# BLOCK5.net
KiCad netlist of a schematic drawn in Altium Designer
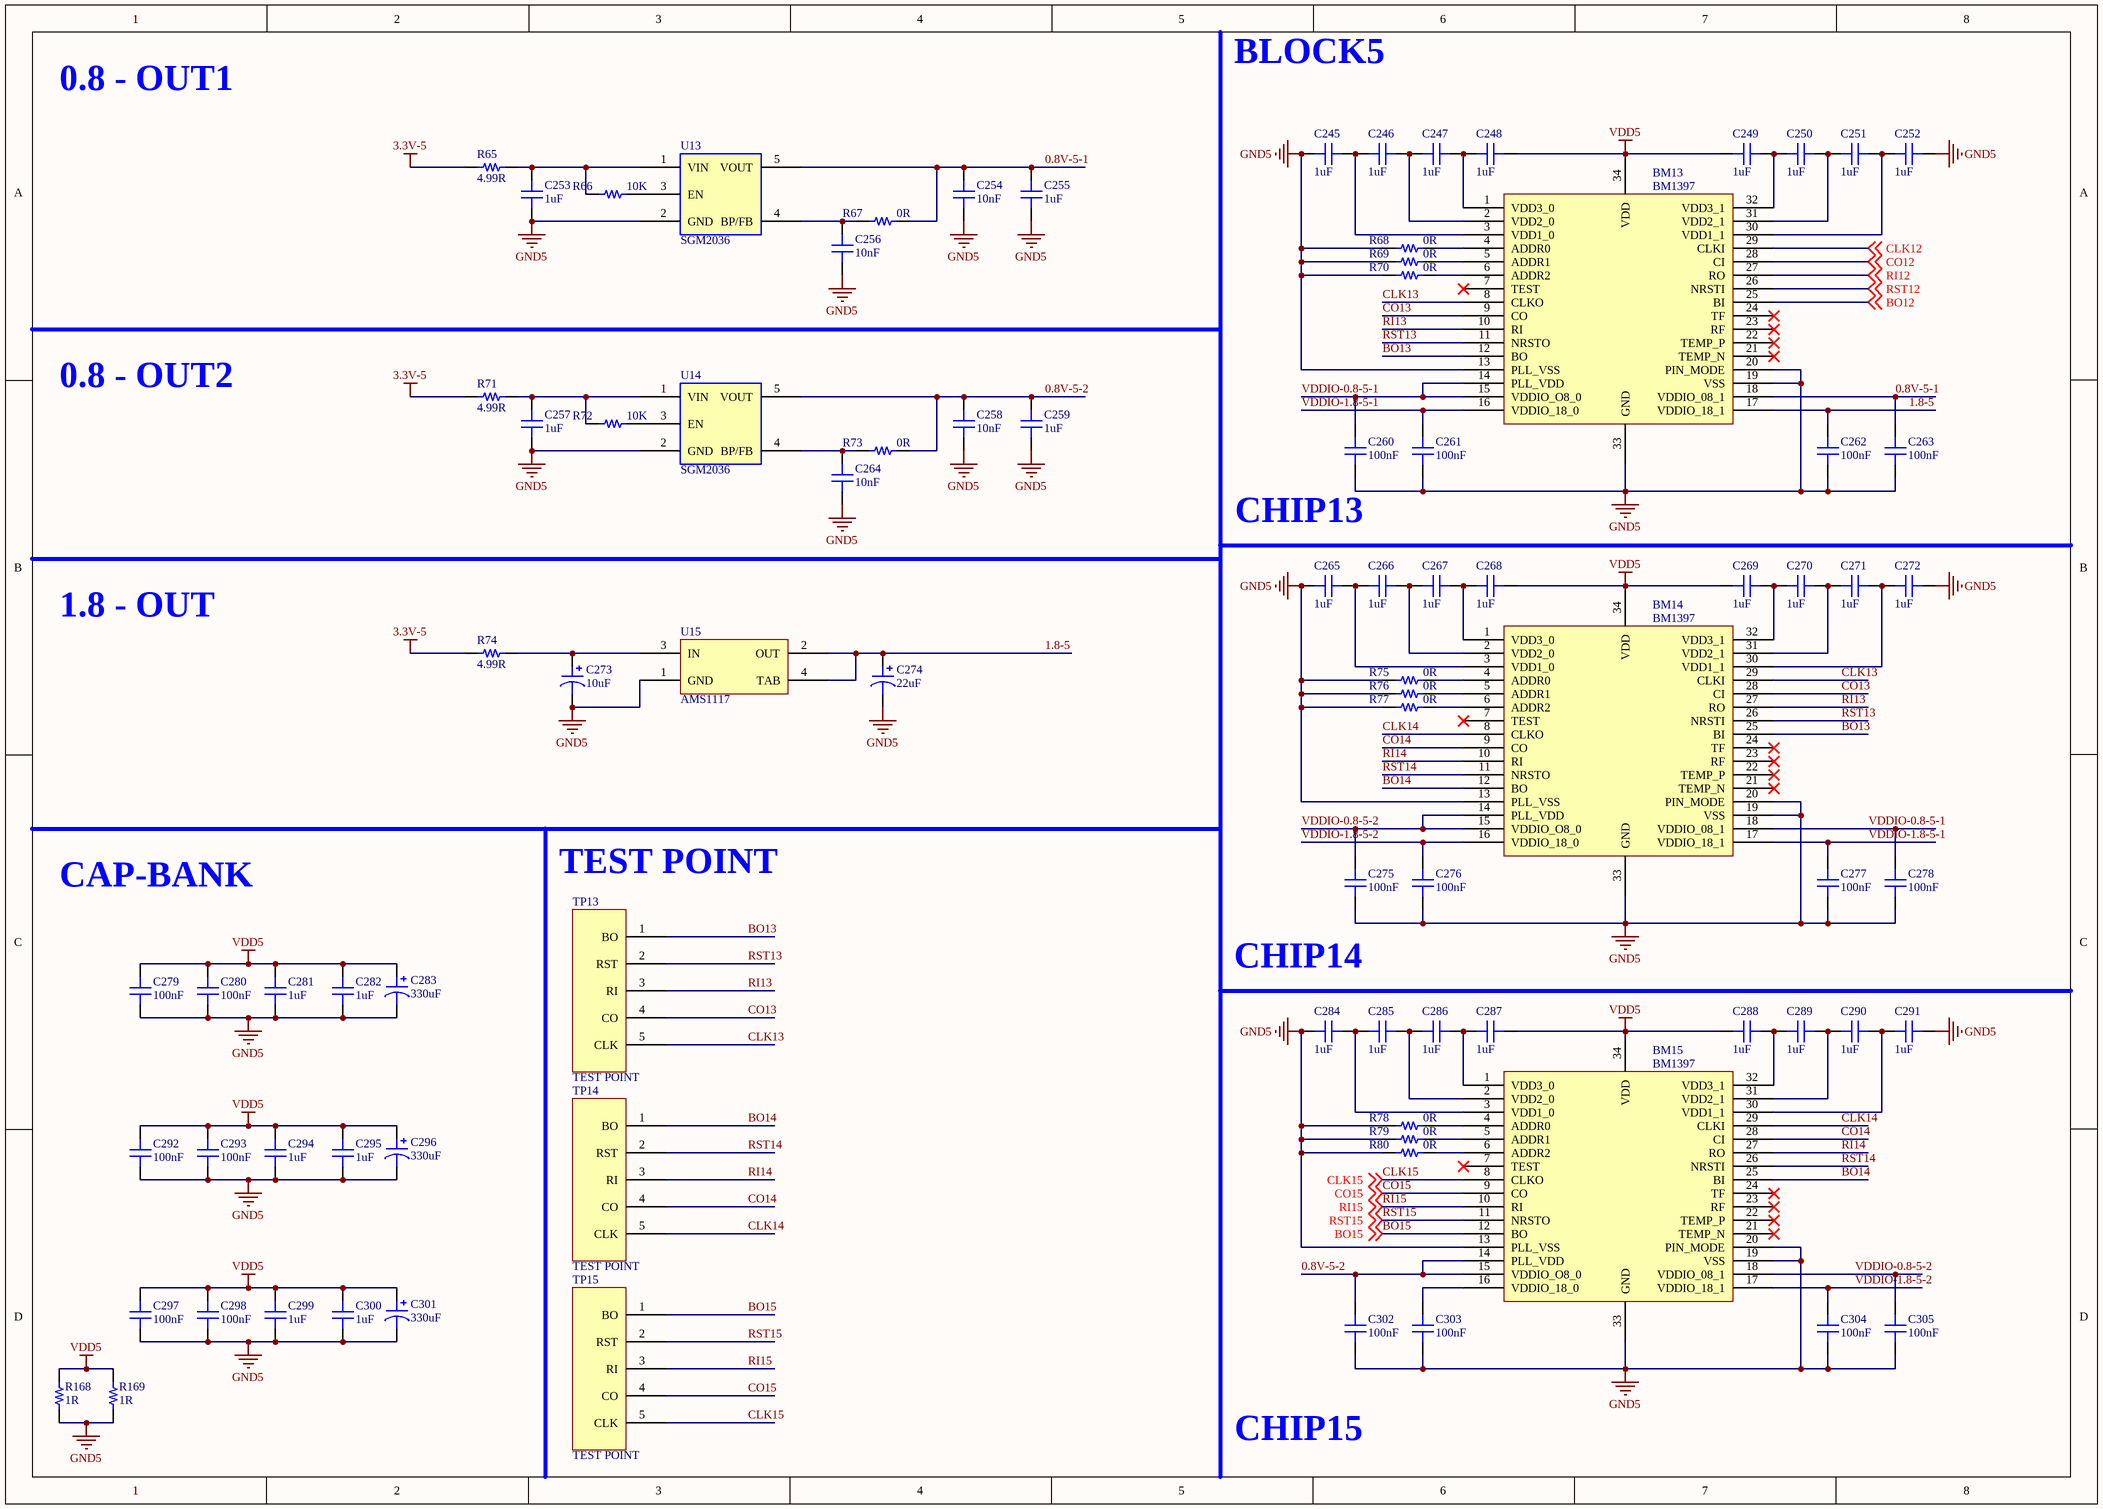
[diagram p0: BLOCK5.SchDoc]

(export (version "E")
  (design (tool "Eeschema 10.0.6"))
  (components
    (comp (ref "BM13") (value "BM1397") (footprint "BM1387") (libsource (lib "Miner_8TH") (part "BM1397_0")))
    (comp (ref "BM14") (value "BM1397") (footprint "BM1387") (libsource (lib "Miner_8TH") (part "BM1397_0")))
    (comp (ref "BM15") (value "BM1397") (footprint "BM1387") (libsource (lib "Miner_8TH") (part "BM1397_0")))
    (comp (ref "C245") (value "1uF") (footprint "CAP-SMD-0603") (libsource (lib "Miner_8TH") (part "CAP")))
    (comp (ref "C246") (value "1uF") (footprint "CAP-SMD-0603") (libsource (lib "Miner_8TH") (part "CAP")))
    (comp (ref "C247") (value "1uF") (footprint "CAP-SMD-0603") (libsource (lib "Miner_8TH") (part "CAP")))
    (comp (ref "C248") (value "1uF") (footprint "CAP-SMD-0603") (libsource (lib "Miner_8TH") (part "CAP")))
    (comp (ref "C249") (value "1uF") (footprint "CAP-SMD-0603") (libsource (lib "Miner_8TH") (part "CAP")))
    (comp (ref "C250") (value "1uF") (footprint "CAP-SMD-0603") (libsource (lib "Miner_8TH") (part "CAP")))
    (comp (ref "C251") (value "1uF") (footprint "CAP-SMD-0603") (libsource (lib "Miner_8TH") (part "CAP")))
    (comp (ref "C252") (value "1uF") (footprint "CAP-SMD-0603") (libsource (lib "Miner_8TH") (part "CAP")))
    (comp (ref "C253") (value "1uF") (footprint "CAP_SMD_0805") (libsource (lib "Miner_8TH") (part "CAP")))
    (comp (ref "C254") (value "10nF") (footprint "CAP_SMD_0805") (libsource (lib "Miner_8TH") (part "CAP")))
    (comp (ref "C255") (value "1uF") (footprint "CAP_SMD_0805") (libsource (lib "Miner_8TH") (part "CAP")))
    (comp (ref "C256") (value "10nF") (footprint "CAP_SMD_0805") (libsource (lib "Miner_8TH") (part "CAP")))
    (comp (ref "C257") (value "1uF") (footprint "CAP_SMD_0805") (libsource (lib "Miner_8TH") (part "CAP")))
    (comp (ref "C258") (value "10nF") (footprint "CAP_SMD_0805") (libsource (lib "Miner_8TH") (part "CAP")))
    (comp (ref "C259") (value "1uF") (footprint "CAP_SMD_0805") (libsource (lib "Miner_8TH") (part "CAP")))
    (comp (ref "C260") (value "100nF") (footprint "CAP_SMD_0805") (libsource (lib "Miner_8TH") (part "CAP")))
    (comp (ref "C261") (value "100nF") (footprint "CAP_SMD_0805") (libsource (lib "Miner_8TH") (part "CAP")))
    (comp (ref "C262") (value "100nF") (footprint "CAP_SMD_0805") (libsource (lib "Miner_8TH") (part "CAP")))
    (comp (ref "C263") (value "100nF") (footprint "CAP_SMD_0805") (libsource (lib "Miner_8TH") (part "CAP")))
    (comp (ref "C264") (value "10nF") (footprint "CAP_SMD_0805") (libsource (lib "Miner_8TH") (part "CAP")))
    (comp (ref "C265") (value "1uF") (footprint "CAP-SMD-0603") (libsource (lib "Miner_8TH") (part "CAP")))
    (comp (ref "C266") (value "1uF") (footprint "CAP-SMD-0603") (libsource (lib "Miner_8TH") (part "CAP")))
    (comp (ref "C267") (value "1uF") (footprint "CAP-SMD-0603") (libsource (lib "Miner_8TH") (part "CAP")))
    (comp (ref "C268") (value "1uF") (footprint "CAP-SMD-0603") (libsource (lib "Miner_8TH") (part "CAP")))
    (comp (ref "C269") (value "1uF") (footprint "CAP-SMD-0603") (libsource (lib "Miner_8TH") (part "CAP")))
    (comp (ref "C270") (value "1uF") (footprint "CAP-SMD-0603") (libsource (lib "Miner_8TH") (part "CAP")))
    (comp (ref "C271") (value "1uF") (footprint "CAP-SMD-0603") (libsource (lib "Miner_8TH") (part "CAP")))
    (comp (ref "C272") (value "1uF") (footprint "CAP-SMD-0603") (libsource (lib "Miner_8TH") (part "CAP")))
    (comp (ref "C273")
      (value "10uF")
      (footprint "CAP-TAN-CASE-A")
      (libsource (lib "Miner_8TH") (part "POLARIZED CAP"))
    )
    (comp (ref "C274")
      (value "22uF")
      (footprint "CAP-TAN-CASE-A")
      (libsource (lib "Miner_8TH") (part "POLARIZED CAP"))
    )
    (comp (ref "C275") (value "100nF") (footprint "CAP_SMD_0805") (libsource (lib "Miner_8TH") (part "CAP")))
    (comp (ref "C276") (value "100nF") (footprint "CAP_SMD_0805") (libsource (lib "Miner_8TH") (part "CAP")))
    (comp (ref "C277") (value "100nF") (footprint "CAP_SMD_0805") (libsource (lib "Miner_8TH") (part "CAP")))
    (comp (ref "C278") (value "100nF") (footprint "CAP_SMD_0805") (libsource (lib "Miner_8TH") (part "CAP")))
    (comp (ref "C279") (value "100nF") (footprint "CAP_SMD_0805") (libsource (lib "Miner_8TH") (part "CAP")))
    (comp (ref "C280") (value "100nF") (footprint "CAP_SMD_0805") (libsource (lib "Miner_8TH") (part "CAP")))
    (comp (ref "C281") (value "1uF") (footprint "CAP_SMD_0805") (libsource (lib "Miner_8TH") (part "CAP")))
    (comp (ref "C282") (value "1uF") (footprint "CAP_SMD_0805") (libsource (lib "Miner_8TH") (part "CAP")))
    (comp (ref "C283")
      (value "330uF")
      (footprint "CAP-TAN-CASE-E")
      (libsource (lib "Miner_8TH") (part "POLARIZED CAP"))
    )
    (comp (ref "C284") (value "1uF") (footprint "CAP-SMD-0603") (libsource (lib "Miner_8TH") (part "CAP")))
    (comp (ref "C285") (value "1uF") (footprint "CAP-SMD-0603") (libsource (lib "Miner_8TH") (part "CAP")))
    (comp (ref "C286") (value "1uF") (footprint "CAP-SMD-0603") (libsource (lib "Miner_8TH") (part "CAP")))
    (comp (ref "C287") (value "1uF") (footprint "CAP-SMD-0603") (libsource (lib "Miner_8TH") (part "CAP")))
    (comp (ref "C288") (value "1uF") (footprint "CAP-SMD-0603") (libsource (lib "Miner_8TH") (part "CAP")))
    (comp (ref "C289") (value "1uF") (footprint "CAP-SMD-0603") (libsource (lib "Miner_8TH") (part "CAP")))
    (comp (ref "C290") (value "1uF") (footprint "CAP-SMD-0603") (libsource (lib "Miner_8TH") (part "CAP")))
    (comp (ref "C291") (value "1uF") (footprint "CAP-SMD-0603") (libsource (lib "Miner_8TH") (part "CAP")))
    (comp (ref "C292") (value "100nF") (footprint "CAP_SMD_0805") (libsource (lib "Miner_8TH") (part "CAP")))
    (comp (ref "C293") (value "100nF") (footprint "CAP_SMD_0805") (libsource (lib "Miner_8TH") (part "CAP")))
    (comp (ref "C294") (value "1uF") (footprint "CAP_SMD_0805") (libsource (lib "Miner_8TH") (part "CAP")))
    (comp (ref "C295") (value "1uF") (footprint "CAP_SMD_0805") (libsource (lib "Miner_8TH") (part "CAP")))
    (comp (ref "C296")
      (value "330uF")
      (footprint "CAP-TAN-CASE-E")
      (libsource (lib "Miner_8TH") (part "POLARIZED CAP"))
    )
    (comp (ref "C297") (value "100nF") (footprint "CAP_SMD_0805") (libsource (lib "Miner_8TH") (part "CAP")))
    (comp (ref "C298") (value "100nF") (footprint "CAP_SMD_0805") (libsource (lib "Miner_8TH") (part "CAP")))
    (comp (ref "C299") (value "1uF") (footprint "CAP_SMD_0805") (libsource (lib "Miner_8TH") (part "CAP")))
    (comp (ref "C300") (value "1uF") (footprint "CAP_SMD_0805") (libsource (lib "Miner_8TH") (part "CAP")))
    (comp (ref "C301")
      (value "330uF")
      (footprint "CAP-TAN-CASE-E")
      (libsource (lib "Miner_8TH") (part "POLARIZED CAP"))
    )
    (comp (ref "C302") (value "100nF") (footprint "CAP_SMD_0805") (libsource (lib "Miner_8TH") (part "CAP")))
    (comp (ref "C303") (value "100nF") (footprint "CAP_SMD_0805") (libsource (lib "Miner_8TH") (part "CAP")))
    (comp (ref "C304") (value "100nF") (footprint "CAP_SMD_0805") (libsource (lib "Miner_8TH") (part "CAP")))
    (comp (ref "C305") (value "100nF") (footprint "CAP_SMD_0805") (libsource (lib "Miner_8TH") (part "CAP")))
    (comp (ref "R65") (value "4.99R") (footprint "RES-SMD-1206") (libsource (lib "Miner_8TH") (part "RES")))
    (comp (ref "R66") (value "10K") (footprint "RES-SMD-0402") (libsource (lib "Miner_8TH") (part "RES")))
    (comp (ref "R67") (value "0R") (footprint "RES-SMD-0402") (libsource (lib "Miner_8TH") (part "RES")))
    (comp (ref "R68") (value "0R") (footprint "RES-SMD-0402") (libsource (lib "Miner_8TH") (part "RES")))
    (comp (ref "R69") (value "0R") (footprint "RES-SMD-0402") (libsource (lib "Miner_8TH") (part "RES")))
    (comp (ref "R70") (value "0R") (footprint "RES-SMD-0402") (libsource (lib "Miner_8TH") (part "RES")))
    (comp (ref "R71") (value "4.99R") (footprint "RES-SMD-1206") (libsource (lib "Miner_8TH") (part "RES")))
    (comp (ref "R72") (value "10K") (footprint "RES-SMD-0402") (libsource (lib "Miner_8TH") (part "RES")))
    (comp (ref "R73") (value "0R") (footprint "RES-SMD-0402") (libsource (lib "Miner_8TH") (part "RES")))
    (comp (ref "R74") (value "4.99R") (footprint "RES-SMD-1206") (libsource (lib "Miner_8TH") (part "RES")))
    (comp (ref "R75") (value "0R") (footprint "RES-SMD-0402") (libsource (lib "Miner_8TH") (part "RES")))
    (comp (ref "R76") (value "0R") (footprint "RES-SMD-0402") (libsource (lib "Miner_8TH") (part "RES")))
    (comp (ref "R77") (value "0R") (footprint "RES-SMD-0402") (libsource (lib "Miner_8TH") (part "RES")))
    (comp (ref "R78") (value "0R") (footprint "RES-SMD-0402") (libsource (lib "Miner_8TH") (part "RES")))
    (comp (ref "R79") (value "0R") (footprint "RES-SMD-0402") (libsource (lib "Miner_8TH") (part "RES")))
    (comp (ref "R80") (value "0R") (footprint "RES-SMD-0402") (libsource (lib "Miner_8TH") (part "RES")))
    (comp (ref "R168") (value "1R") (footprint "RES-SMD-1210") (libsource (lib "Miner_8TH") (part "RES")))
    (comp (ref "R169") (value "1R") (footprint "RES-SMD-1210") (libsource (lib "Miner_8TH") (part "RES")))
    (comp (ref "TP13")
      (value "TEST POINT")
      (footprint "TEST_POINT")
      (libsource (lib "Miner_8TH") (part "TEST POINT"))
    )
    (comp (ref "TP14")
      (value "TEST POINT")
      (footprint "TEST_POINT")
      (libsource (lib "Miner_8TH") (part "TEST POINT"))
    )
    (comp (ref "TP15")
      (value "TEST POINT")
      (footprint "TEST_POINT")
      (libsource (lib "Miner_8TH") (part "TEST POINT"))
    )
    (comp (ref "U13")
      (value "SGM2036")
      (footprint "SOT23-5PIN")
      (libsource (lib "Miner_8TH") (part "SGM2036"))
    )
    (comp (ref "U14")
      (value "SGM2036")
      (footprint "SOT23-5PIN")
      (libsource (lib "Miner_8TH") (part "SGM2036"))
    )
    (comp (ref "U15") (value "AMS1117") (footprint "AMS1117") (libsource (lib "Miner_8TH") (part "AMS1117")))
  )
  (nets
    (net (code "1") (name "/0.8V-5-1") (class "Default")
      (node (ref "BM13") (pin "18") (pinfunction "VDDIO_08_1_18") (pintype "passive"))
      (node (ref "C254") (pin "2") (pinfunction "2_2") (pintype "passive"))
      (node (ref "C255") (pin "2") (pinfunction "2_2") (pintype "passive"))
      (node (ref "C263") (pin "2") (pinfunction "2_2") (pintype "passive"))
      (node (ref "R67") (pin "2") (pinfunction "2_2") (pintype "passive"))
      (node (ref "U13") (pin "5") (pinfunction "VOUT_5") (pintype "passive"))
    )
    (net (code "2") (name "/0.8V-5-2") (class "Default")
      (node (ref "BM15") (pin "14") (pinfunction "PLL_VDD_14") (pintype "passive"))
      (node (ref "BM15") (pin "15") (pinfunction "VDDIO_O8_0_15") (pintype "passive"))
      (node (ref "C258") (pin "2") (pinfunction "2_2") (pintype "passive"))
      (node (ref "C259") (pin "2") (pinfunction "2_2") (pintype "passive"))
      (node (ref "C302") (pin "2") (pinfunction "2_2") (pintype "passive"))
      (node (ref "R73") (pin "2") (pinfunction "2_2") (pintype "passive"))
      (node (ref "U14") (pin "5") (pinfunction "VOUT_5") (pintype "passive"))
    )
    (net (code "3") (name "/1.8-5") (class "Default")
      (node (ref "BM13") (pin "17") (pinfunction "VDDIO_18_1_17") (pintype "passive"))
      (node (ref "C262") (pin "2") (pinfunction "2_2") (pintype "passive"))
      (node (ref "C274") (pin "1") (pinfunction "1_1") (pintype "passive"))
      (node (ref "U15") (pin "2") (pinfunction "OUT_2") (pintype "passive"))
      (node (ref "U15") (pin "4") (pinfunction "TAB_4") (pintype "passive"))
    )
    (net (code "4") (name "/BO13") (class "Default")
      (node (ref "BM13") (pin "12") (pinfunction "BO_12") (pintype "passive"))
      (node (ref "BM14") (pin "25") (pinfunction "BI_25") (pintype "passive"))
      (node (ref "TP13") (pin "1") (pinfunction "BO_1") (pintype "passive"))
    )
    (net (code "5") (name "/BO14") (class "Default")
      (node (ref "BM14") (pin "12") (pinfunction "BO_12") (pintype "passive"))
      (node (ref "BM15") (pin "25") (pinfunction "BI_25") (pintype "passive"))
      (node (ref "TP14") (pin "1") (pinfunction "BO_1") (pintype "passive"))
    )
    (net (code "6") (name "/CLK13") (class "Default")
      (node (ref "BM13") (pin "8") (pinfunction "CLKO_8") (pintype "passive"))
      (node (ref "BM14") (pin "29") (pinfunction "CLKI_29") (pintype "passive"))
      (node (ref "TP13") (pin "5") (pinfunction "CLK_5") (pintype "passive"))
    )
    (net (code "7") (name "/CLK14") (class "Default")
      (node (ref "BM14") (pin "8") (pinfunction "CLKO_8") (pintype "passive"))
      (node (ref "BM15") (pin "29") (pinfunction "CLKI_29") (pintype "passive"))
      (node (ref "TP14") (pin "5") (pinfunction "CLK_5") (pintype "passive"))
    )
    (net (code "8") (name "/CO13") (class "Default")
      (node (ref "BM13") (pin "9") (pinfunction "CO_9") (pintype "passive"))
      (node (ref "BM14") (pin "28") (pinfunction "CI_28") (pintype "passive"))
      (node (ref "TP13") (pin "4") (pinfunction "CO_4") (pintype "passive"))
    )
    (net (code "9") (name "/CO14") (class "Default")
      (node (ref "BM14") (pin "9") (pinfunction "CO_9") (pintype "passive"))
      (node (ref "BM15") (pin "28") (pinfunction "CI_28") (pintype "passive"))
      (node (ref "TP14") (pin "4") (pinfunction "CO_4") (pintype "passive"))
    )
    (net (code "10") (name "/RI13") (class "Default")
      (node (ref "BM13") (pin "10") (pinfunction "RI_10") (pintype "passive"))
      (node (ref "BM14") (pin "27") (pinfunction "RO_27") (pintype "passive"))
      (node (ref "TP13") (pin "3") (pinfunction "RI_3") (pintype "passive"))
    )
    (net (code "11") (name "/RI14") (class "Default")
      (node (ref "BM14") (pin "10") (pinfunction "RI_10") (pintype "passive"))
      (node (ref "BM15") (pin "27") (pinfunction "RO_27") (pintype "passive"))
      (node (ref "TP14") (pin "3") (pinfunction "RI_3") (pintype "passive"))
    )
    (net (code "12") (name "/RST13") (class "Default")
      (node (ref "BM13") (pin "11") (pinfunction "NRSTO_11") (pintype "passive"))
      (node (ref "BM14") (pin "26") (pinfunction "NRSTI_26") (pintype "passive"))
      (node (ref "TP13") (pin "2") (pinfunction "RST_2") (pintype "passive"))
    )
    (net (code "13") (name "/RST14") (class "Default")
      (node (ref "BM14") (pin "11") (pinfunction "NRSTO_11") (pintype "passive"))
      (node (ref "BM15") (pin "26") (pinfunction "NRSTI_26") (pintype "passive"))
      (node (ref "TP14") (pin "2") (pinfunction "RST_2") (pintype "passive"))
    )
    (net (code "14") (name "/VDDIO-0.8-5-1") (class "Default")
      (node (ref "BM13") (pin "14") (pinfunction "PLL_VDD_14") (pintype "passive"))
      (node (ref "BM13") (pin "15") (pinfunction "VDDIO_O8_0_15") (pintype "passive"))
      (node (ref "BM14") (pin "18") (pinfunction "VDDIO_08_1_18") (pintype "passive"))
      (node (ref "C260") (pin "2") (pinfunction "2_2") (pintype "passive"))
      (node (ref "C278") (pin "2") (pinfunction "2_2") (pintype "passive"))
    )
    (net (code "15") (name "/VDDIO-0.8-5-2") (class "Default")
      (node (ref "BM14") (pin "14") (pinfunction "PLL_VDD_14") (pintype "passive"))
      (node (ref "BM14") (pin "15") (pinfunction "VDDIO_O8_0_15") (pintype "passive"))
      (node (ref "BM15") (pin "18") (pinfunction "VDDIO_08_1_18") (pintype "passive"))
      (node (ref "C275") (pin "2") (pinfunction "2_2") (pintype "passive"))
      (node (ref "C305") (pin "2") (pinfunction "2_2") (pintype "passive"))
    )
    (net (code "16") (name "/VDDIO-1.8-5-1") (class "Default")
      (node (ref "BM13") (pin "16") (pinfunction "VDDIO_18_0_16") (pintype "passive"))
      (node (ref "BM14") (pin "17") (pinfunction "VDDIO_18_1_17") (pintype "passive"))
      (node (ref "C261") (pin "2") (pinfunction "2_2") (pintype "passive"))
      (node (ref "C277") (pin "2") (pinfunction "2_2") (pintype "passive"))
    )
    (net (code "17") (name "/VDDIO-1.8-5-2") (class "Default")
      (node (ref "BM14") (pin "16") (pinfunction "VDDIO_18_0_16") (pintype "passive"))
      (node (ref "BM15") (pin "17") (pinfunction "VDDIO_18_1_17") (pintype "passive"))
      (node (ref "C276") (pin "2") (pinfunction "2_2") (pintype "passive"))
      (node (ref "C304") (pin "2") (pinfunction "2_2") (pintype "passive"))
    )
    (net (code "18") (name "3.3V-5") (class "Default")
      (node (ref "R65") (pin "1") (pinfunction "1_1") (pintype "passive"))
      (node (ref "R71") (pin "1") (pinfunction "1_1") (pintype "passive"))
      (node (ref "R74") (pin "1") (pinfunction "1_1") (pintype "passive"))
    )
    (net (code "19") (name "BO12") (class "Default")
      (node (ref "BM13") (pin "25") (pinfunction "BI_25") (pintype "passive"))
    )
    (net (code "20") (name "BO15") (class "Default")
      (node (ref "BM15") (pin "12") (pinfunction "BO_12") (pintype "passive"))
      (node (ref "TP15") (pin "1") (pinfunction "BO_1") (pintype "passive"))
    )
    (net (code "21") (name "CLK12") (class "Default")
      (node (ref "BM13") (pin "29") (pinfunction "CLKI_29") (pintype "passive"))
    )
    (net (code "22") (name "CLK15") (class "Default")
      (node (ref "BM15") (pin "8") (pinfunction "CLKO_8") (pintype "passive"))
      (node (ref "TP15") (pin "5") (pinfunction "CLK_5") (pintype "passive"))
    )
    (net (code "23") (name "CO12") (class "Default")
      (node (ref "BM13") (pin "28") (pinfunction "CI_28") (pintype "passive"))
    )
    (net (code "24") (name "CO15") (class "Default")
      (node (ref "BM15") (pin "9") (pinfunction "CO_9") (pintype "passive"))
      (node (ref "TP15") (pin "4") (pinfunction "CO_4") (pintype "passive"))
    )
    (net (code "25") (name "GND5") (class "Default")
      (node (ref "BM13") (pin "13") (pinfunction "PLL_VSS_13") (pintype "passive"))
      (node (ref "BM13") (pin "19") (pinfunction "VSS_19") (pintype "passive"))
      (node (ref "BM13") (pin "20") (pinfunction "PIN_MODE_20") (pintype "passive"))
      (node (ref "BM13") (pin "33") (pinfunction "GND_33") (pintype "passive"))
      (node (ref "BM14") (pin "13") (pinfunction "PLL_VSS_13") (pintype "passive"))
      (node (ref "BM14") (pin "19") (pinfunction "VSS_19") (pintype "passive"))
      (node (ref "BM14") (pin "20") (pinfunction "PIN_MODE_20") (pintype "passive"))
      (node (ref "BM14") (pin "33") (pinfunction "GND_33") (pintype "passive"))
      (node (ref "BM15") (pin "13") (pinfunction "PLL_VSS_13") (pintype "passive"))
      (node (ref "BM15") (pin "19") (pinfunction "VSS_19") (pintype "passive"))
      (node (ref "BM15") (pin "20") (pinfunction "PIN_MODE_20") (pintype "passive"))
      (node (ref "BM15") (pin "33") (pinfunction "GND_33") (pintype "passive"))
      (node (ref "C245") (pin "1") (pinfunction "1_1") (pintype "passive"))
      (node (ref "C252") (pin "2") (pinfunction "2_2") (pintype "passive"))
      (node (ref "C253") (pin "1") (pinfunction "1_1") (pintype "passive"))
      (node (ref "C254") (pin "1") (pinfunction "1_1") (pintype "passive"))
      (node (ref "C255") (pin "1") (pinfunction "1_1") (pintype "passive"))
      (node (ref "C256") (pin "1") (pinfunction "1_1") (pintype "passive"))
      (node (ref "C257") (pin "1") (pinfunction "1_1") (pintype "passive"))
      (node (ref "C258") (pin "1") (pinfunction "1_1") (pintype "passive"))
      (node (ref "C259") (pin "1") (pinfunction "1_1") (pintype "passive"))
      (node (ref "C260") (pin "1") (pinfunction "1_1") (pintype "passive"))
      (node (ref "C261") (pin "1") (pinfunction "1_1") (pintype "passive"))
      (node (ref "C262") (pin "1") (pinfunction "1_1") (pintype "passive"))
      (node (ref "C263") (pin "1") (pinfunction "1_1") (pintype "passive"))
      (node (ref "C264") (pin "1") (pinfunction "1_1") (pintype "passive"))
      (node (ref "C265") (pin "1") (pinfunction "1_1") (pintype "passive"))
      (node (ref "C272") (pin "2") (pinfunction "2_2") (pintype "passive"))
      (node (ref "C273") (pin "2") (pinfunction "2_2") (pintype "passive"))
      (node (ref "C274") (pin "2") (pinfunction "2_2") (pintype "passive"))
      (node (ref "C275") (pin "1") (pinfunction "1_1") (pintype "passive"))
      (node (ref "C276") (pin "1") (pinfunction "1_1") (pintype "passive"))
      (node (ref "C277") (pin "1") (pinfunction "1_1") (pintype "passive"))
      (node (ref "C278") (pin "1") (pinfunction "1_1") (pintype "passive"))
      (node (ref "C279") (pin "1") (pinfunction "1_1") (pintype "passive"))
      (node (ref "C280") (pin "1") (pinfunction "1_1") (pintype "passive"))
      (node (ref "C281") (pin "1") (pinfunction "1_1") (pintype "passive"))
      (node (ref "C282") (pin "1") (pinfunction "1_1") (pintype "passive"))
      (node (ref "C283") (pin "2") (pinfunction "2_2") (pintype "passive"))
      (node (ref "C284") (pin "1") (pinfunction "1_1") (pintype "passive"))
      (node (ref "C291") (pin "2") (pinfunction "2_2") (pintype "passive"))
      (node (ref "C292") (pin "1") (pinfunction "1_1") (pintype "passive"))
      (node (ref "C293") (pin "1") (pinfunction "1_1") (pintype "passive"))
      (node (ref "C294") (pin "1") (pinfunction "1_1") (pintype "passive"))
      (node (ref "C295") (pin "1") (pinfunction "1_1") (pintype "passive"))
      (node (ref "C296") (pin "2") (pinfunction "2_2") (pintype "passive"))
      (node (ref "C297") (pin "1") (pinfunction "1_1") (pintype "passive"))
      (node (ref "C298") (pin "1") (pinfunction "1_1") (pintype "passive"))
      (node (ref "C299") (pin "1") (pinfunction "1_1") (pintype "passive"))
      (node (ref "C300") (pin "1") (pinfunction "1_1") (pintype "passive"))
      (node (ref "C301") (pin "2") (pinfunction "2_2") (pintype "passive"))
      (node (ref "C302") (pin "1") (pinfunction "1_1") (pintype "passive"))
      (node (ref "C303") (pin "1") (pinfunction "1_1") (pintype "passive"))
      (node (ref "C304") (pin "1") (pinfunction "1_1") (pintype "passive"))
      (node (ref "C305") (pin "1") (pinfunction "1_1") (pintype "passive"))
      (node (ref "R168") (pin "1") (pinfunction "1_1") (pintype "passive"))
      (node (ref "R169") (pin "1") (pinfunction "1_1") (pintype "passive"))
      (node (ref "R68") (pin "1") (pinfunction "1_1") (pintype "passive"))
      (node (ref "R69") (pin "1") (pinfunction "1_1") (pintype "passive"))
      (node (ref "R70") (pin "1") (pinfunction "1_1") (pintype "passive"))
      (node (ref "R75") (pin "1") (pinfunction "1_1") (pintype "passive"))
      (node (ref "R76") (pin "1") (pinfunction "1_1") (pintype "passive"))
      (node (ref "R77") (pin "1") (pinfunction "1_1") (pintype "passive"))
      (node (ref "R78") (pin "1") (pinfunction "1_1") (pintype "passive"))
      (node (ref "R79") (pin "1") (pinfunction "1_1") (pintype "passive"))
      (node (ref "R80") (pin "1") (pinfunction "1_1") (pintype "passive"))
      (node (ref "U13") (pin "2") (pinfunction "GND_2") (pintype "passive"))
      (node (ref "U14") (pin "2") (pinfunction "GND_2") (pintype "passive"))
      (node (ref "U15") (pin "1") (pinfunction "GND_1") (pintype "passive"))
    )
    (net (code "26") (name "Net-(BM13-ADDR0)") (class "Default")
      (node (ref "BM13") (pin "4") (pinfunction "ADDR0_4") (pintype "passive"))
      (node (ref "R68") (pin "2") (pinfunction "2_2") (pintype "passive"))
    )
    (net (code "27") (name "Net-(BM13-ADDR1)") (class "Default")
      (node (ref "BM13") (pin "5") (pinfunction "ADDR1_5") (pintype "passive"))
      (node (ref "R69") (pin "2") (pinfunction "2_2") (pintype "passive"))
    )
    (net (code "28") (name "Net-(BM13-ADDR2)") (class "Default")
      (node (ref "BM13") (pin "6") (pinfunction "ADDR2_6") (pintype "passive"))
      (node (ref "R70") (pin "2") (pinfunction "2_2") (pintype "passive"))
    )
    (net (code "29") (name "Net-(BM13-VDD1_0)") (class "Default")
      (node (ref "BM13") (pin "3") (pinfunction "VDD1_0_3") (pintype "passive"))
      (node (ref "C245") (pin "2") (pinfunction "2_2") (pintype "passive"))
      (node (ref "C246") (pin "1") (pinfunction "1_1") (pintype "passive"))
    )
    (net (code "30") (name "Net-(BM13-VDD1_1)") (class "Default")
      (node (ref "BM13") (pin "30") (pinfunction "VDD1_1_30") (pintype "passive"))
      (node (ref "C251") (pin "2") (pinfunction "2_2") (pintype "passive"))
      (node (ref "C252") (pin "1") (pinfunction "1_1") (pintype "passive"))
    )
    (net (code "31") (name "Net-(BM13-VDD2_0)") (class "Default")
      (node (ref "BM13") (pin "2") (pinfunction "VDD2_0_2") (pintype "passive"))
      (node (ref "C246") (pin "2") (pinfunction "2_2") (pintype "passive"))
      (node (ref "C247") (pin "1") (pinfunction "1_1") (pintype "passive"))
    )
    (net (code "32") (name "Net-(BM13-VDD2_1)") (class "Default")
      (node (ref "BM13") (pin "31") (pinfunction "VDD2_1_31") (pintype "passive"))
      (node (ref "C250") (pin "2") (pinfunction "2_2") (pintype "passive"))
      (node (ref "C251") (pin "1") (pinfunction "1_1") (pintype "passive"))
    )
    (net (code "33") (name "Net-(BM13-VDD3_0)") (class "Default")
      (node (ref "BM13") (pin "1") (pinfunction "VDD3_0_1") (pintype "passive"))
      (node (ref "C247") (pin "2") (pinfunction "2_2") (pintype "passive"))
      (node (ref "C248") (pin "1") (pinfunction "1_1") (pintype "passive"))
    )
    (net (code "34") (name "Net-(BM13-VDD3_1)") (class "Default")
      (node (ref "BM13") (pin "32") (pinfunction "VDD3_1_32") (pintype "passive"))
      (node (ref "C249") (pin "2") (pinfunction "2_2") (pintype "passive"))
      (node (ref "C250") (pin "1") (pinfunction "1_1") (pintype "passive"))
    )
    (net (code "35") (name "Net-(BM14-ADDR0)") (class "Default")
      (node (ref "BM14") (pin "4") (pinfunction "ADDR0_4") (pintype "passive"))
      (node (ref "R75") (pin "2") (pinfunction "2_2") (pintype "passive"))
    )
    (net (code "36") (name "Net-(BM14-ADDR1)") (class "Default")
      (node (ref "BM14") (pin "5") (pinfunction "ADDR1_5") (pintype "passive"))
      (node (ref "R76") (pin "2") (pinfunction "2_2") (pintype "passive"))
    )
    (net (code "37") (name "Net-(BM14-ADDR2)") (class "Default")
      (node (ref "BM14") (pin "6") (pinfunction "ADDR2_6") (pintype "passive"))
      (node (ref "R77") (pin "2") (pinfunction "2_2") (pintype "passive"))
    )
    (net (code "38") (name "Net-(BM14-VDD1_0)") (class "Default")
      (node (ref "BM14") (pin "3") (pinfunction "VDD1_0_3") (pintype "passive"))
      (node (ref "C265") (pin "2") (pinfunction "2_2") (pintype "passive"))
      (node (ref "C266") (pin "1") (pinfunction "1_1") (pintype "passive"))
    )
    (net (code "39") (name "Net-(BM14-VDD1_1)") (class "Default")
      (node (ref "BM14") (pin "30") (pinfunction "VDD1_1_30") (pintype "passive"))
      (node (ref "C271") (pin "2") (pinfunction "2_2") (pintype "passive"))
      (node (ref "C272") (pin "1") (pinfunction "1_1") (pintype "passive"))
    )
    (net (code "40") (name "Net-(BM14-VDD2_0)") (class "Default")
      (node (ref "BM14") (pin "2") (pinfunction "VDD2_0_2") (pintype "passive"))
      (node (ref "C266") (pin "2") (pinfunction "2_2") (pintype "passive"))
      (node (ref "C267") (pin "1") (pinfunction "1_1") (pintype "passive"))
    )
    (net (code "41") (name "Net-(BM14-VDD2_1)") (class "Default")
      (node (ref "BM14") (pin "31") (pinfunction "VDD2_1_31") (pintype "passive"))
      (node (ref "C270") (pin "2") (pinfunction "2_2") (pintype "passive"))
      (node (ref "C271") (pin "1") (pinfunction "1_1") (pintype "passive"))
    )
    (net (code "42") (name "Net-(BM14-VDD3_0)") (class "Default")
      (node (ref "BM14") (pin "1") (pinfunction "VDD3_0_1") (pintype "passive"))
      (node (ref "C267") (pin "2") (pinfunction "2_2") (pintype "passive"))
      (node (ref "C268") (pin "1") (pinfunction "1_1") (pintype "passive"))
    )
    (net (code "43") (name "Net-(BM14-VDD3_1)") (class "Default")
      (node (ref "BM14") (pin "32") (pinfunction "VDD3_1_32") (pintype "passive"))
      (node (ref "C269") (pin "2") (pinfunction "2_2") (pintype "passive"))
      (node (ref "C270") (pin "1") (pinfunction "1_1") (pintype "passive"))
    )
    (net (code "44") (name "Net-(BM15-ADDR0)") (class "Default")
      (node (ref "BM15") (pin "4") (pinfunction "ADDR0_4") (pintype "passive"))
      (node (ref "R78") (pin "2") (pinfunction "2_2") (pintype "passive"))
    )
    (net (code "45") (name "Net-(BM15-ADDR1)") (class "Default")
      (node (ref "BM15") (pin "5") (pinfunction "ADDR1_5") (pintype "passive"))
      (node (ref "R79") (pin "2") (pinfunction "2_2") (pintype "passive"))
    )
    (net (code "46") (name "Net-(BM15-ADDR2)") (class "Default")
      (node (ref "BM15") (pin "6") (pinfunction "ADDR2_6") (pintype "passive"))
      (node (ref "R80") (pin "2") (pinfunction "2_2") (pintype "passive"))
    )
    (net (code "47") (name "Net-(BM15-VDD1_0)") (class "Default")
      (node (ref "BM15") (pin "3") (pinfunction "VDD1_0_3") (pintype "passive"))
      (node (ref "C284") (pin "2") (pinfunction "2_2") (pintype "passive"))
      (node (ref "C285") (pin "1") (pinfunction "1_1") (pintype "passive"))
    )
    (net (code "48") (name "Net-(BM15-VDD1_1)") (class "Default")
      (node (ref "BM15") (pin "30") (pinfunction "VDD1_1_30") (pintype "passive"))
      (node (ref "C290") (pin "2") (pinfunction "2_2") (pintype "passive"))
      (node (ref "C291") (pin "1") (pinfunction "1_1") (pintype "passive"))
    )
    (net (code "49") (name "Net-(BM15-VDD2_0)") (class "Default")
      (node (ref "BM15") (pin "2") (pinfunction "VDD2_0_2") (pintype "passive"))
      (node (ref "C285") (pin "2") (pinfunction "2_2") (pintype "passive"))
      (node (ref "C286") (pin "1") (pinfunction "1_1") (pintype "passive"))
    )
    (net (code "50") (name "Net-(BM15-VDD2_1)") (class "Default")
      (node (ref "BM15") (pin "31") (pinfunction "VDD2_1_31") (pintype "passive"))
      (node (ref "C289") (pin "2") (pinfunction "2_2") (pintype "passive"))
      (node (ref "C290") (pin "1") (pinfunction "1_1") (pintype "passive"))
    )
    (net (code "51") (name "Net-(BM15-VDD3_0)") (class "Default")
      (node (ref "BM15") (pin "1") (pinfunction "VDD3_0_1") (pintype "passive"))
      (node (ref "C286") (pin "2") (pinfunction "2_2") (pintype "passive"))
      (node (ref "C287") (pin "1") (pinfunction "1_1") (pintype "passive"))
    )
    (net (code "52") (name "Net-(BM15-VDD3_1)") (class "Default")
      (node (ref "BM15") (pin "32") (pinfunction "VDD3_1_32") (pintype "passive"))
      (node (ref "C288") (pin "2") (pinfunction "2_2") (pintype "passive"))
      (node (ref "C289") (pin "1") (pinfunction "1_1") (pintype "passive"))
    )
    (net (code "53") (name "Net-(BM15-VDDIO_18_0)") (class "Default")
      (node (ref "BM15") (pin "16") (pinfunction "VDDIO_18_0_16") (pintype "passive"))
      (node (ref "C303") (pin "2") (pinfunction "2_2") (pintype "passive"))
    )
    (net (code "54") (name "Net-(U13-BP{slash}FB)") (class "Default")
      (node (ref "C256") (pin "2") (pinfunction "2_2") (pintype "passive"))
      (node (ref "R67") (pin "1") (pinfunction "1_1") (pintype "passive"))
      (node (ref "U13") (pin "4") (pinfunction "BP/FB_4") (pintype "passive"))
    )
    (net (code "55") (name "Net-(U13-EN)") (class "Default")
      (node (ref "R66") (pin "2") (pinfunction "2_2") (pintype "passive"))
      (node (ref "U13") (pin "3") (pinfunction "EN_3") (pintype "passive"))
    )
    (net (code "56") (name "Net-(U13-VIN)") (class "Default")
      (node (ref "C253") (pin "2") (pinfunction "2_2") (pintype "passive"))
      (node (ref "R65") (pin "2") (pinfunction "2_2") (pintype "passive"))
      (node (ref "R66") (pin "1") (pinfunction "1_1") (pintype "passive"))
      (node (ref "U13") (pin "1") (pinfunction "VIN_1") (pintype "passive"))
    )
    (net (code "57") (name "Net-(U14-BP{slash}FB)") (class "Default")
      (node (ref "C264") (pin "2") (pinfunction "2_2") (pintype "passive"))
      (node (ref "R73") (pin "1") (pinfunction "1_1") (pintype "passive"))
      (node (ref "U14") (pin "4") (pinfunction "BP/FB_4") (pintype "passive"))
    )
    (net (code "58") (name "Net-(U14-EN)") (class "Default")
      (node (ref "R72") (pin "2") (pinfunction "2_2") (pintype "passive"))
      (node (ref "U14") (pin "3") (pinfunction "EN_3") (pintype "passive"))
    )
    (net (code "59") (name "Net-(U14-VIN)") (class "Default")
      (node (ref "C257") (pin "2") (pinfunction "2_2") (pintype "passive"))
      (node (ref "R71") (pin "2") (pinfunction "2_2") (pintype "passive"))
      (node (ref "R72") (pin "1") (pinfunction "1_1") (pintype "passive"))
      (node (ref "U14") (pin "1") (pinfunction "VIN_1") (pintype "passive"))
    )
    (net (code "60") (name "Net-(U15-IN)") (class "Default")
      (node (ref "C273") (pin "1") (pinfunction "1_1") (pintype "passive"))
      (node (ref "R74") (pin "2") (pinfunction "2_2") (pintype "passive"))
      (node (ref "U15") (pin "3") (pinfunction "IN_3") (pintype "passive"))
    )
    (net (code "61") (name "RI12") (class "Default")
      (node (ref "BM13") (pin "27") (pinfunction "RO_27") (pintype "passive"))
    )
    (net (code "62") (name "RI15") (class "Default")
      (node (ref "BM15") (pin "10") (pinfunction "RI_10") (pintype "passive"))
      (node (ref "TP15") (pin "3") (pinfunction "RI_3") (pintype "passive"))
    )
    (net (code "63") (name "RST12") (class "Default")
      (node (ref "BM13") (pin "26") (pinfunction "NRSTI_26") (pintype "passive"))
    )
    (net (code "64") (name "RST15") (class "Default")
      (node (ref "BM15") (pin "11") (pinfunction "NRSTO_11") (pintype "passive"))
      (node (ref "TP15") (pin "2") (pinfunction "RST_2") (pintype "passive"))
    )
    (net (code "65") (name "VDD5") (class "Default")
      (node (ref "BM13") (pin "34") (pinfunction "VDD_34") (pintype "passive"))
      (node (ref "BM14") (pin "34") (pinfunction "VDD_34") (pintype "passive"))
      (node (ref "BM15") (pin "34") (pinfunction "VDD_34") (pintype "passive"))
      (node (ref "C248") (pin "2") (pinfunction "2_2") (pintype "passive"))
      (node (ref "C249") (pin "1") (pinfunction "1_1") (pintype "passive"))
      (node (ref "C268") (pin "2") (pinfunction "2_2") (pintype "passive"))
      (node (ref "C269") (pin "1") (pinfunction "1_1") (pintype "passive"))
      (node (ref "C279") (pin "2") (pinfunction "2_2") (pintype "passive"))
      (node (ref "C280") (pin "2") (pinfunction "2_2") (pintype "passive"))
      (node (ref "C281") (pin "2") (pinfunction "2_2") (pintype "passive"))
      (node (ref "C282") (pin "2") (pinfunction "2_2") (pintype "passive"))
      (node (ref "C283") (pin "1") (pinfunction "1_1") (pintype "passive"))
      (node (ref "C287") (pin "2") (pinfunction "2_2") (pintype "passive"))
      (node (ref "C288") (pin "1") (pinfunction "1_1") (pintype "passive"))
      (node (ref "C292") (pin "2") (pinfunction "2_2") (pintype "passive"))
      (node (ref "C293") (pin "2") (pinfunction "2_2") (pintype "passive"))
      (node (ref "C294") (pin "2") (pinfunction "2_2") (pintype "passive"))
      (node (ref "C295") (pin "2") (pinfunction "2_2") (pintype "passive"))
      (node (ref "C296") (pin "1") (pinfunction "1_1") (pintype "passive"))
      (node (ref "C297") (pin "2") (pinfunction "2_2") (pintype "passive"))
      (node (ref "C298") (pin "2") (pinfunction "2_2") (pintype "passive"))
      (node (ref "C299") (pin "2") (pinfunction "2_2") (pintype "passive"))
      (node (ref "C300") (pin "2") (pinfunction "2_2") (pintype "passive"))
      (node (ref "C301") (pin "1") (pinfunction "1_1") (pintype "passive"))
      (node (ref "R168") (pin "2") (pinfunction "2_2") (pintype "passive"))
      (node (ref "R169") (pin "2") (pinfunction "2_2") (pintype "passive"))
    )
    (net (code "66") (name "unconnected-(BM13-RF-Pad23)") (class "Default")
      (node (ref "BM13") (pin "23") (pinfunction "RF_23") (pintype "passive+no_connect"))
    )
    (net (code "67") (name "unconnected-(BM13-TEMP_N-Pad21)") (class "Default")
      (node (ref "BM13") (pin "21") (pinfunction "TEMP_N_21") (pintype "passive+no_connect"))
    )
    (net (code "68") (name "unconnected-(BM13-TEMP_P-Pad22)") (class "Default")
      (node (ref "BM13") (pin "22") (pinfunction "TEMP_P_22") (pintype "passive+no_connect"))
    )
    (net (code "69") (name "unconnected-(BM13-TEST-Pad7)") (class "Default")
      (node (ref "BM13") (pin "7") (pinfunction "TEST_7") (pintype "passive+no_connect"))
    )
    (net (code "70") (name "unconnected-(BM13-TF-Pad24)") (class "Default")
      (node (ref "BM13") (pin "24") (pinfunction "TF_24") (pintype "passive+no_connect"))
    )
    (net (code "71") (name "unconnected-(BM14-RF-Pad23)") (class "Default")
      (node (ref "BM14") (pin "23") (pinfunction "RF_23") (pintype "passive+no_connect"))
    )
    (net (code "72") (name "unconnected-(BM14-TEMP_N-Pad21)") (class "Default")
      (node (ref "BM14") (pin "21") (pinfunction "TEMP_N_21") (pintype "passive+no_connect"))
    )
    (net (code "73") (name "unconnected-(BM14-TEMP_P-Pad22)") (class "Default")
      (node (ref "BM14") (pin "22") (pinfunction "TEMP_P_22") (pintype "passive+no_connect"))
    )
    (net (code "74") (name "unconnected-(BM14-TEST-Pad7)") (class "Default")
      (node (ref "BM14") (pin "7") (pinfunction "TEST_7") (pintype "passive+no_connect"))
    )
    (net (code "75") (name "unconnected-(BM14-TF-Pad24)") (class "Default")
      (node (ref "BM14") (pin "24") (pinfunction "TF_24") (pintype "passive+no_connect"))
    )
    (net (code "76") (name "unconnected-(BM15-RF-Pad23)") (class "Default")
      (node (ref "BM15") (pin "23") (pinfunction "RF_23") (pintype "passive+no_connect"))
    )
    (net (code "77") (name "unconnected-(BM15-TEMP_N-Pad21)") (class "Default")
      (node (ref "BM15") (pin "21") (pinfunction "TEMP_N_21") (pintype "passive+no_connect"))
    )
    (net (code "78") (name "unconnected-(BM15-TEMP_P-Pad22)") (class "Default")
      (node (ref "BM15") (pin "22") (pinfunction "TEMP_P_22") (pintype "passive+no_connect"))
    )
    (net (code "79") (name "unconnected-(BM15-TEST-Pad7)") (class "Default")
      (node (ref "BM15") (pin "7") (pinfunction "TEST_7") (pintype "passive+no_connect"))
    )
    (net (code "80") (name "unconnected-(BM15-TF-Pad24)") (class "Default")
      (node (ref "BM15") (pin "24") (pinfunction "TF_24") (pintype "passive+no_connect"))
    )
  )
)
